# ADMP401-CMS1206.net
KiCad netlist of a schematic drawn in EAGLE
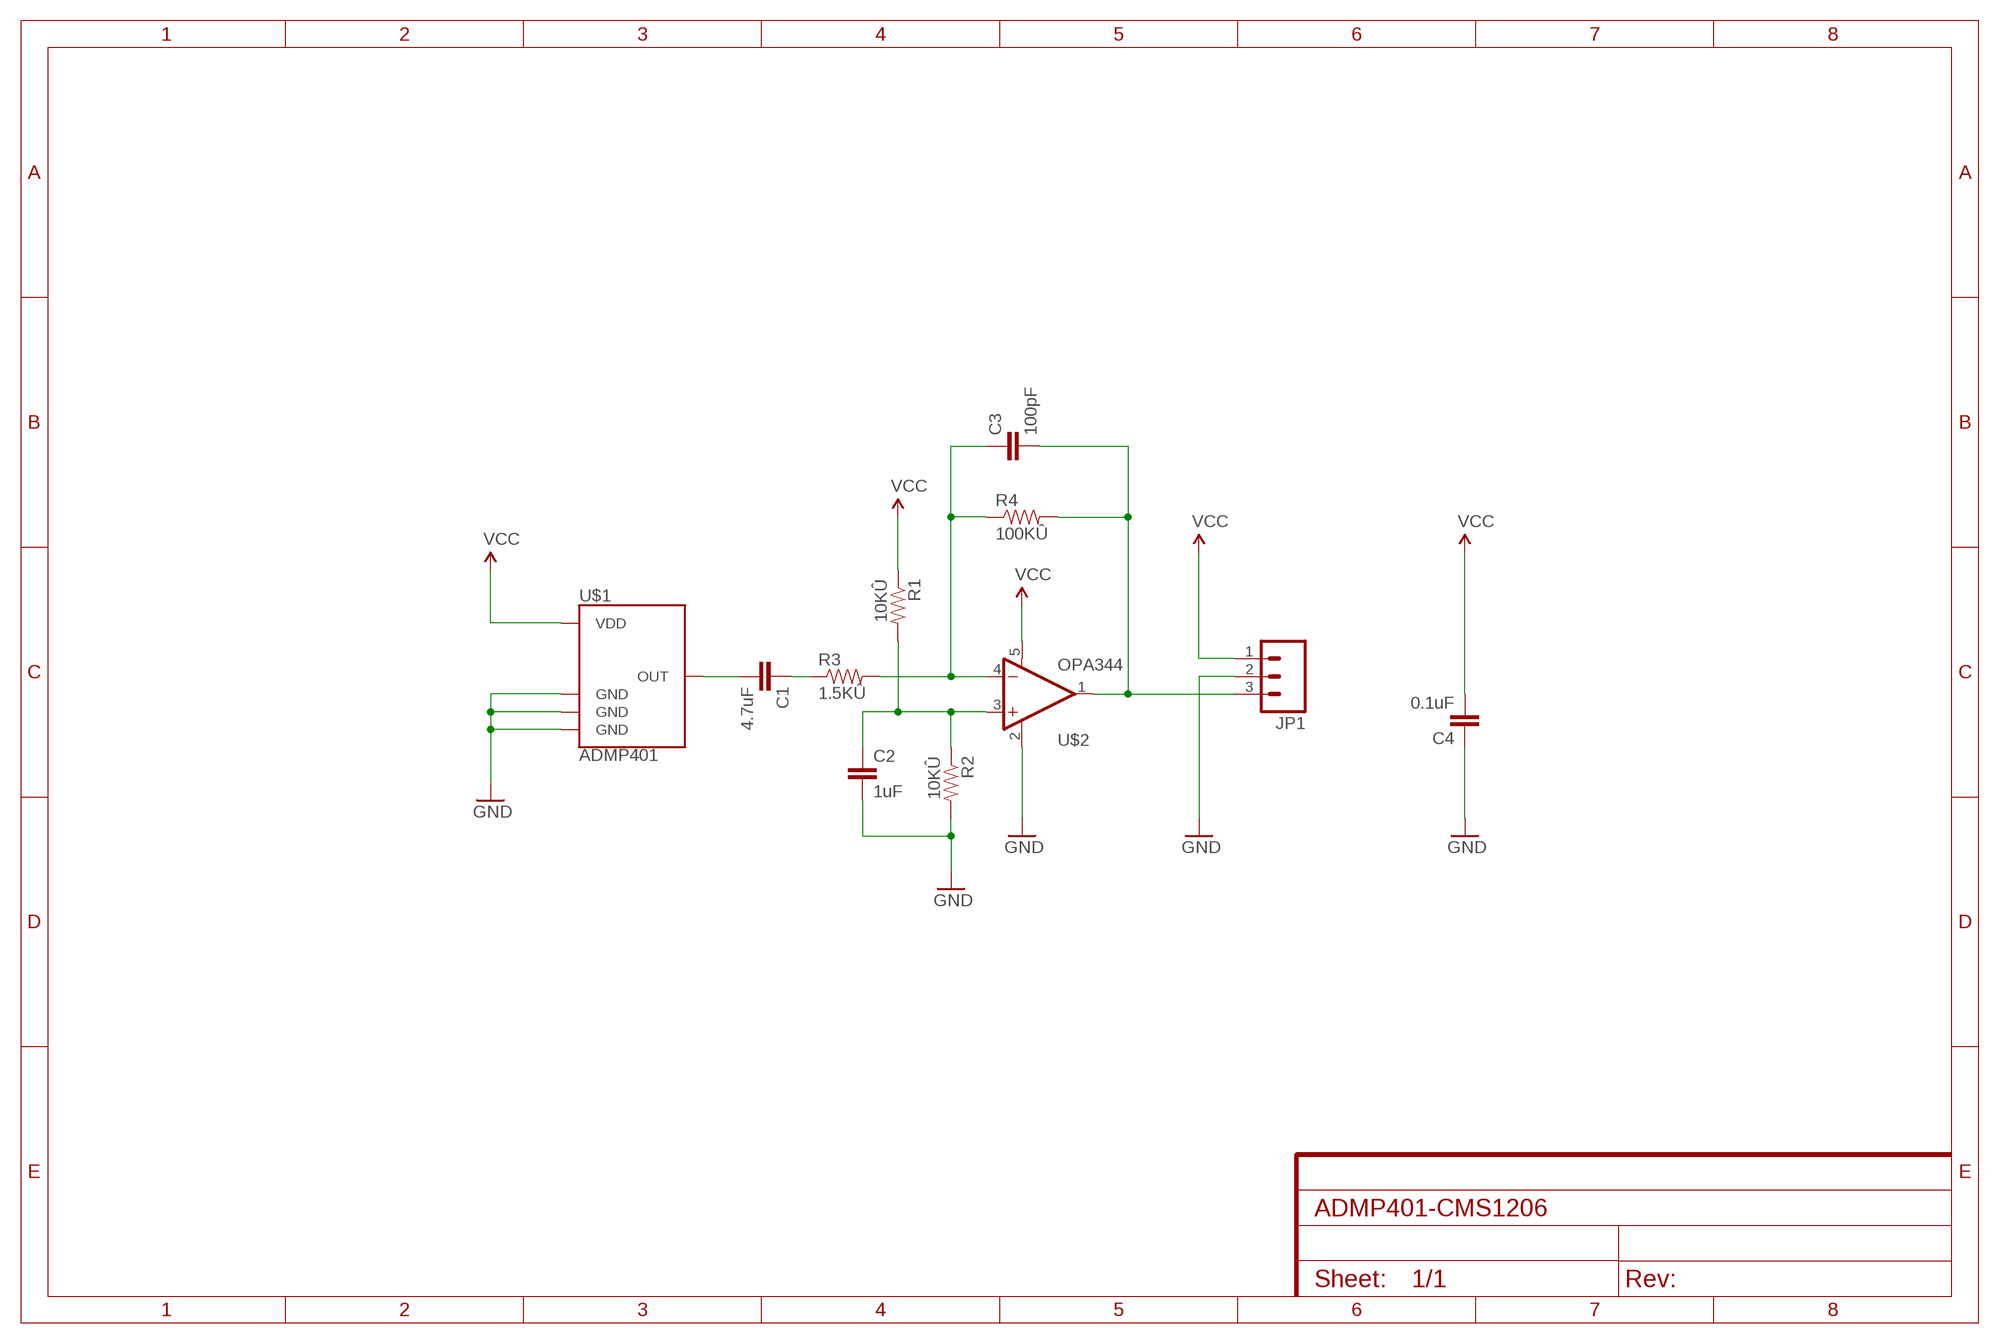
[diagram p0: schematic, sheet 1]

(export (version "E")
  (design (tool "Eeschema 10.0.6"))
  (components
    (comp (ref "C1")
      (value "4.7uF")
      (footprint "eagle-import:1206")
      (libsource (lib "eagle-import") (part "CAP1206"))
    )
    (comp (ref "C2")
      (value "1uF")
      (footprint "eagle-import:1206")
      (libsource (lib "eagle-import") (part "CAP1206"))
    )
    (comp (ref "C3")
      (value "100pF")
      (footprint "eagle-import:1206")
      (libsource (lib "eagle-import") (part "CAP1206"))
    )
    (comp (ref "C4")
      (value "0.1uF")
      (footprint "eagle-import:1206")
      (libsource (lib "eagle-import") (part "CAP1206"))
    )
    (comp (ref "JP1")
      (value "M03PTH")
      (footprint "eagle-import:1X03")
      (libsource (lib "eagle-import") (part "M03PTH"))
    )
    (comp (ref "R1")
      (value "10KÛ")
      (footprint "eagle-import:1206")
      (libsource (lib "eagle-import") (part "RESISTOR1206"))
    )
    (comp (ref "R2")
      (value "10KÛ")
      (footprint "eagle-import:1206")
      (libsource (lib "eagle-import") (part "RESISTOR1206"))
    )
    (comp (ref "R3")
      (value "1.5KÛ")
      (footprint "eagle-import:1206")
      (libsource (lib "eagle-import") (part "RESISTOR1206"))
    )
    (comp (ref "R4")
      (value "100KÛ")
      (footprint "eagle-import:1206")
      (libsource (lib "eagle-import") (part "RESISTOR1206"))
    )
    (comp (ref "U$1")
      (value "ADMP401")
      (footprint "eagle-import:ADMP401")
      (libsource (lib "eagle-import") (part "ADMP401"))
    )
    (comp (ref "U$2")
      (value "OPA344")
      (footprint "eagle-import:SOT23-5")
      (libsource (lib "eagle-import") (part "OPA344"))
    )
  )
  (nets
    (net (code "1") (name "GND") (class "Default")
      (node (ref "C2") (pin "2") (pinfunction "2_2") (pintype "passive"))
      (node (ref "C4") (pin "1") (pinfunction "1_1") (pintype "passive"))
      (node (ref "JP1") (pin "2") (pinfunction "2_2") (pintype "passive"))
      (node (ref "R2") (pin "2") (pinfunction "2_2") (pintype "passive"))
      (node (ref "U$1") (pin "2") (pinfunction "GND_2") (pintype "bidirectional"))
      (node (ref "U$1") (pin "4") (pinfunction "GND_4") (pintype "bidirectional"))
      (node (ref "U$1") (pin "6") (pinfunction "GND_6") (pintype "bidirectional"))
      (node (ref "U$2") (pin "2") (pinfunction "V-_2") (pintype "power_in"))
    )
    (net (code "2") (name "Net-(C1-Pad1)") (class "Default")
      (node (ref "C1") (pin "1") (pinfunction "1_1") (pintype "passive"))
      (node (ref "R3") (pin "1") (pinfunction "1_1") (pintype "passive"))
    )
    (net (code "3") (name "Net-(U$1-OUT)") (class "Default")
      (node (ref "C1") (pin "2") (pinfunction "2_2") (pintype "passive"))
      (node (ref "U$1") (pin "1") (pinfunction "OUT_1") (pintype "bidirectional"))
    )
    (net (code "4") (name "Net-(U$2-+IN)") (class "Default")
      (node (ref "C2") (pin "1") (pinfunction "1_1") (pintype "passive"))
      (node (ref "R1") (pin "2") (pinfunction "2_2") (pintype "passive"))
      (node (ref "R2") (pin "1") (pinfunction "1_1") (pintype "passive"))
      (node (ref "U$2") (pin "3") (pinfunction "+IN_3") (pintype "input"))
    )
    (net (code "5") (name "Net-(U$2--IN)") (class "Default")
      (node (ref "C3") (pin "1") (pinfunction "1_1") (pintype "passive"))
      (node (ref "R3") (pin "2") (pinfunction "2_2") (pintype "passive"))
      (node (ref "R4") (pin "1") (pinfunction "1_1") (pintype "passive"))
      (node (ref "U$2") (pin "4") (pinfunction "-IN_4") (pintype "input"))
    )
    (net (code "6") (name "Net-(U$2-OUT)") (class "Default")
      (node (ref "C3") (pin "2") (pinfunction "2_2") (pintype "passive"))
      (node (ref "JP1") (pin "3") (pinfunction "3_3") (pintype "passive"))
      (node (ref "R4") (pin "2") (pinfunction "2_2") (pintype "passive"))
      (node (ref "U$2") (pin "1") (pinfunction "OUT_1") (pintype "output"))
    )
    (net (code "7") (name "VCC") (class "Default")
      (node (ref "C4") (pin "2") (pinfunction "2_2") (pintype "passive"))
      (node (ref "JP1") (pin "1") (pinfunction "1_1") (pintype "passive"))
      (node (ref "R1") (pin "1") (pinfunction "1_1") (pintype "passive"))
      (node (ref "U$1") (pin "5") (pinfunction "VDD_5") (pintype "bidirectional"))
      (node (ref "U$2") (pin "5") (pinfunction "V+_5") (pintype "power_in"))
    )
  )
)
